# iF11K.net
KiCad netlist of a schematic drawn in Altium Designer
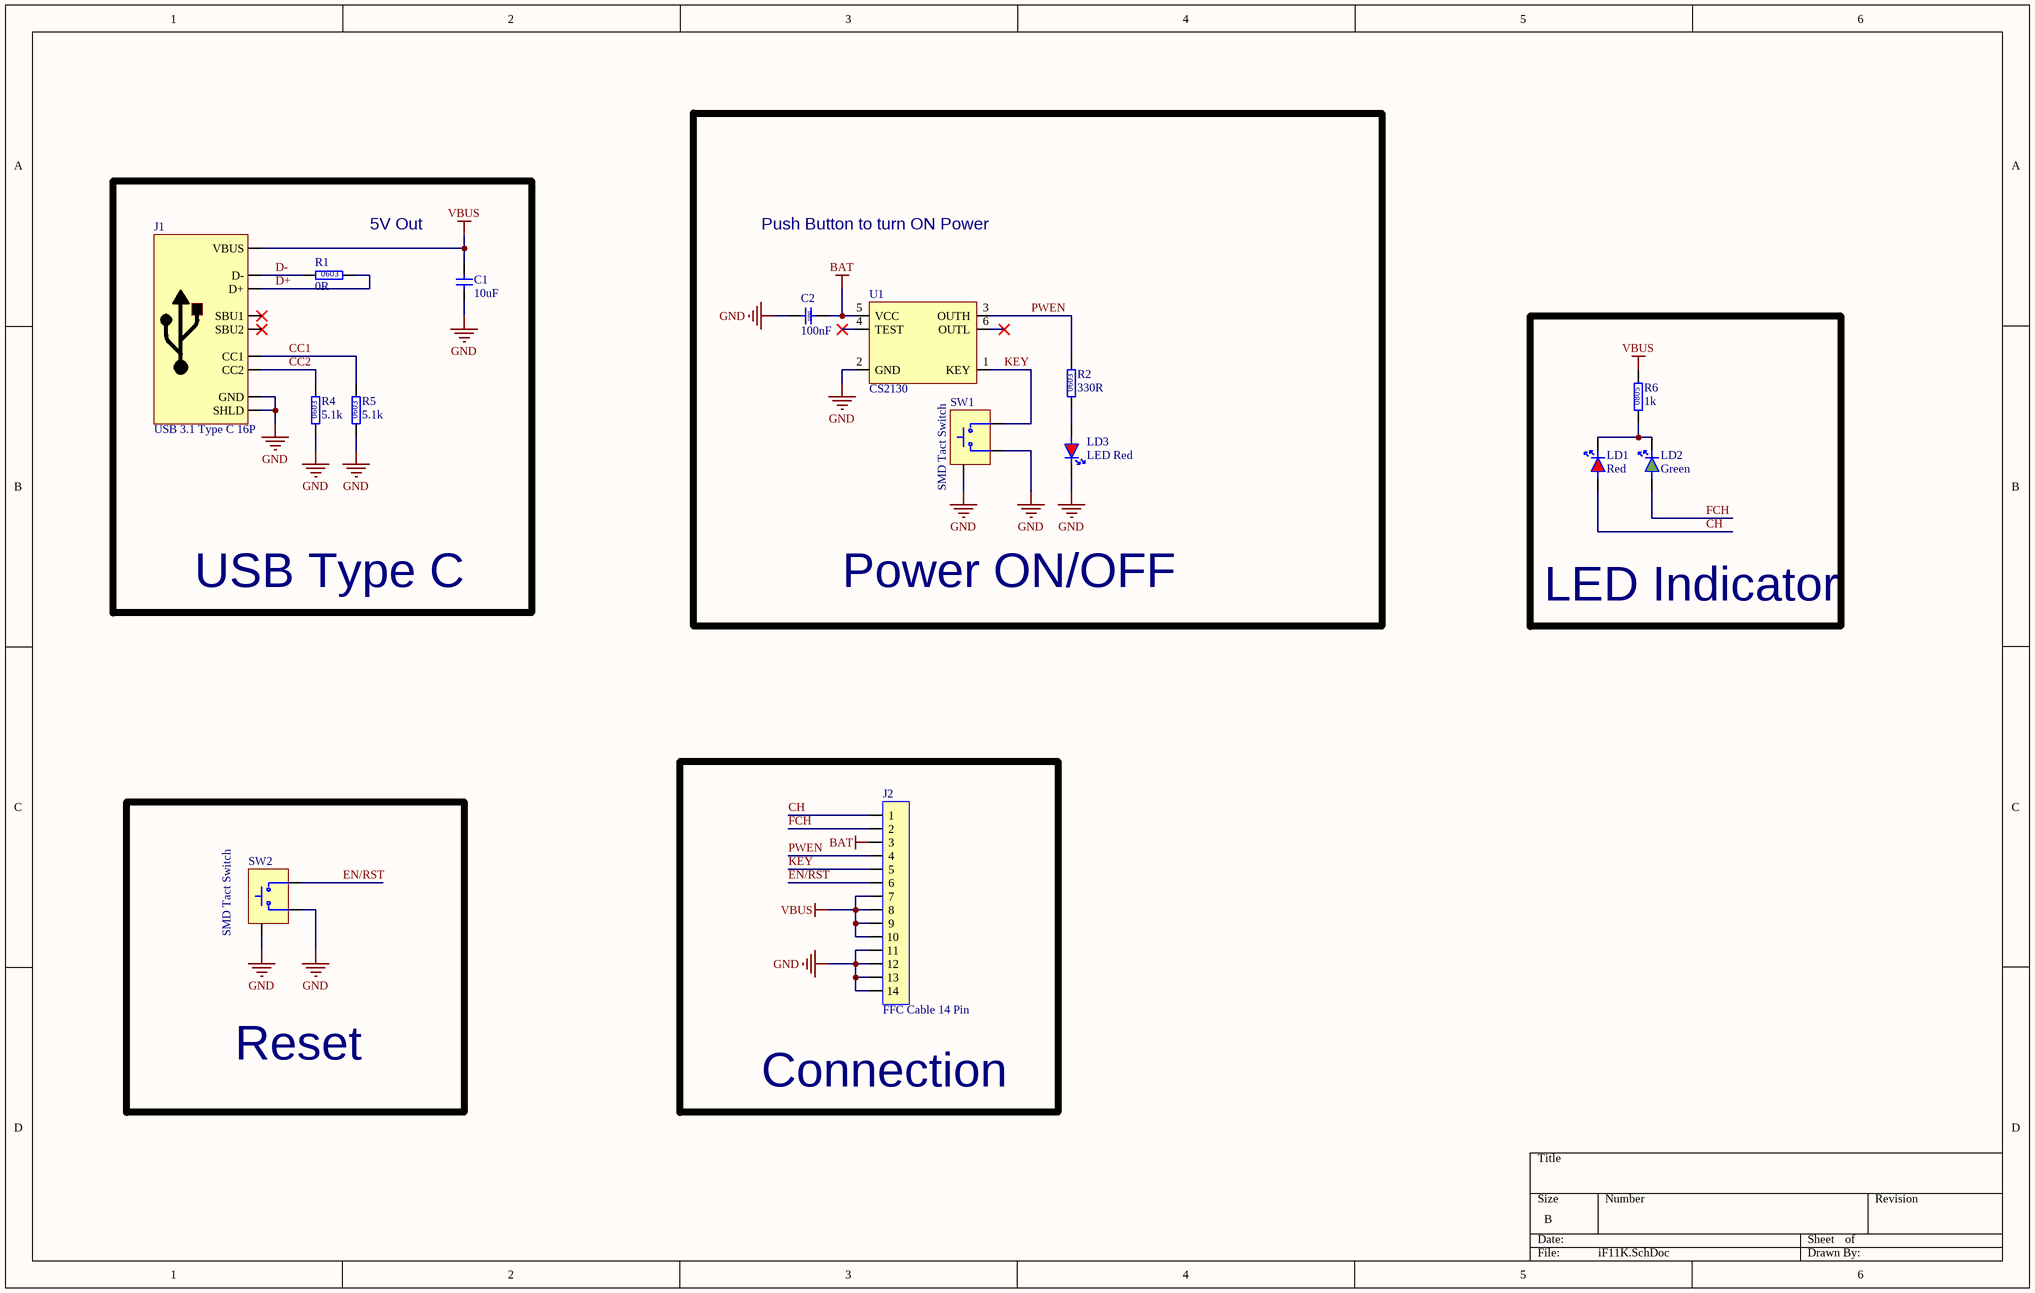
[diagram p0: iF11K.SchDoc]

(export (version "E")
  (design (tool "Eeschema 10.0.6"))
  (components
    (comp (ref "C1")
      (value "10uF")
      (footprint "C0603")
      (description "0603 Package 25V")
      (libsource (lib "Capacitors") (part "Capacitor"))
    )
    (comp (ref "C2")
      (value "100nF")
      (footprint "C0603")
      (description "10% 50V")
      (fields (field (name "PART NO") "W-T-CA-X703N100K50VNT") (field (name "MANUFACTURER") "FENGHUA"))
      (libsource (lib "Rescap") (part "C 0603 100nF 50V"))
    )
    (comp (ref "J1")
      (value "USB 3.1 Type C 16P")
      (footprint "USBC-16P -Upd")
      (description "TYPE-C 16PIN L8.35")
      (fields (field (name "PART NO") "W-T-CN-TYPE-C 16P"))
      (libsource (lib "Connector") (part "USB-C-16P"))
    )
    (comp (ref "J2")
      (value "FFC Cable 14 Pin")
      (footprint "FFC-14-1.25mm")
      (libsource (lib "Connector") (part "FFC14P"))
    )
    (comp (ref "LD1")
      (value "Red")
      (footprint "LED 3mm RED")
      (libsource (lib "Optoelectronics") (part "LED Red"))
    )
    (comp (ref "LD2")
      (value "Green")
      (footprint "LED-0603-GREEN")
      (libsource (lib "Optoelectronics") (part "LED Green"))
    )
    (comp (ref "LD3")
      (value "LED Red")
      (footprint "LED 3mm RED")
      (libsource (lib "Optoelectronics") (part "LED Red"))
    )
    (comp (ref "R1")
      (value "0R")
      (footprint "R0603-LD")
      (description "5%")
      (fields (field (name "PART NO") "W-T-RE-RS03K0RJT") (field (name "MANUFACTURER") "贴片"))
      (libsource (lib "Rescap") (part "R 0603 0R"))
    )
    (comp (ref "R2")
      (value "330R")
      (footprint "R0603-LD")
      (description "5%")
      (fields (field (name "PART NO") "W-T-RE-RS03K331JT"))
      (libsource (lib "Rescap") (part "R 0603 330R"))
    )
    (comp (ref "R4")
      (value "5.1k")
      (footprint "R0603-LD")
      (description "5%")
      (fields (field (name "PART NO") "W-T-RE-RS03K512JT"))
      (libsource (lib "Rescap") (part "R 0603 5.1k"))
    )
    (comp (ref "R5")
      (value "5.1k")
      (footprint "R0603-LD")
      (description "5%")
      (fields (field (name "PART NO") "W-T-RE-RS03K512JT"))
      (libsource (lib "Rescap") (part "R 0603 5.1k"))
    )
    (comp (ref "R6")
      (value "1k")
      (footprint "R0805-LD")
      (description "5%")
      (fields (field (name "PART NO") "W-T-RE-RS05K121JT"))
      (libsource (lib "Rescap") (part "R 0805 1k"))
    )
    (comp (ref "SW1")
      (value "SMD Tact Switch")
      (footprint "Light button")
      (libsource (lib "Switch") (part "soft tact switch"))
    )
    (comp (ref "SW2")
      (value "SMD Tact Switch")
      (footprint "Light button")
      (libsource (lib "Switch") (part "soft tact switch"))
    )
    (comp (ref "U1")
      (value "CS2130")
      (footprint "SOT23-6")
      (description "Single-button switch IC")
      (libsource (lib "mylib2") (part "CS2130"))
    )
  )
  (nets
    (net (code "1") (name "/CC1") (class "Default")
      (node (ref "J1") (pin "4") (pinfunction "CC1_4") (pintype "passive"))
      (node (ref "R5") (pin "2") (pinfunction "2_2") (pintype "passive"))
    )
    (net (code "2") (name "/CC2") (class "Default")
      (node (ref "J1") (pin "8") (pinfunction "CC2_8") (pintype "passive"))
      (node (ref "R4") (pin "2") (pinfunction "2_2") (pintype "passive"))
    )
    (net (code "3") (name "/CH") (class "Default")
      (node (ref "J2") (pin "1") (pinfunction "1_1") (pintype "passive"))
      (node (ref "LD1") (pin "1") (pinfunction "A_1") (pintype "passive"))
    )
    (net (code "4") (name "/D+") (class "Default")
      (node (ref "J1") (pin "6") (pinfunction "D+_6") (pintype "passive"))
      (node (ref "R1") (pin "2") (pinfunction "2_2") (pintype "passive"))
    )
    (net (code "5") (name "/D-") (class "Default")
      (node (ref "J1") (pin "5") (pinfunction "D-_5") (pintype "passive"))
      (node (ref "R1") (pin "1") (pinfunction "1_1") (pintype "passive"))
    )
    (net (code "6") (name "/EN{slash}RST") (class "Default")
      (node (ref "J2") (pin "6") (pinfunction "6_6") (pintype "passive"))
      (node (ref "SW2") (pin "2") (pinfunction "2_2") (pintype "passive"))
    )
    (net (code "7") (name "/FCH") (class "Default")
      (node (ref "J2") (pin "2") (pinfunction "2_2") (pintype "passive"))
      (node (ref "LD2") (pin "1") (pinfunction "A_1") (pintype "passive"))
    )
    (net (code "8") (name "/KEY") (class "Default")
      (node (ref "J2") (pin "5") (pinfunction "5_5") (pintype "passive"))
      (node (ref "SW1") (pin "2") (pinfunction "2_2") (pintype "passive"))
      (node (ref "U1") (pin "1") (pinfunction "KEY_1") (pintype "passive"))
    )
    (net (code "9") (name "/PWEN") (class "Default")
      (node (ref "J2") (pin "4") (pinfunction "4_4") (pintype "passive"))
      (node (ref "R2") (pin "2") (pinfunction "2_2") (pintype "passive"))
      (node (ref "U1") (pin "3") (pinfunction "OUTH_3") (pintype "passive"))
    )
    (net (code "10") (name "BAT") (class "Default")
      (node (ref "C2") (pin "1") (pinfunction "1_1") (pintype "passive"))
      (node (ref "J2") (pin "3") (pinfunction "3_3") (pintype "passive"))
      (node (ref "U1") (pin "5") (pinfunction "VCC_5") (pintype "passive"))
    )
    (net (code "11") (name "GND") (class "Default")
      (node (ref "C1") (pin "1") (pinfunction "1_1") (pintype "passive"))
      (node (ref "C2") (pin "2") (pinfunction "2_2") (pintype "passive"))
      (node (ref "J1") (pin "1") (pinfunction "GND_1") (pintype "passive"))
      (node (ref "J1") (pin "10") (pinfunction "SHLD_10") (pintype "passive"))
      (node (ref "J2") (pin "11") (pinfunction "11_11") (pintype "passive"))
      (node (ref "J2") (pin "12") (pinfunction "12_12") (pintype "passive"))
      (node (ref "J2") (pin "13") (pinfunction "13_13") (pintype "passive"))
      (node (ref "J2") (pin "14") (pinfunction "14_14") (pintype "passive"))
      (node (ref "LD3") (pin "2") (pinfunction "K_2") (pintype "passive"))
      (node (ref "R4") (pin "1") (pinfunction "1_1") (pintype "passive"))
      (node (ref "R5") (pin "1") (pinfunction "1_1") (pintype "passive"))
      (node (ref "SW1") (pin "1") (pinfunction "1_1") (pintype "passive"))
      (node (ref "SW1") (pin "3") (pinfunction "3_3") (pintype "passive"))
      (node (ref "SW2") (pin "1") (pinfunction "1_1") (pintype "passive"))
      (node (ref "SW2") (pin "3") (pinfunction "3_3") (pintype "passive"))
      (node (ref "U1") (pin "2") (pinfunction "GND_2") (pintype "passive"))
    )
    (net (code "12") (name "Net-(LD1-K)") (class "Default")
      (node (ref "LD1") (pin "2") (pinfunction "K_2") (pintype "passive"))
      (node (ref "LD2") (pin "2") (pinfunction "K_2") (pintype "passive"))
      (node (ref "R6") (pin "1") (pinfunction "1_1") (pintype "passive"))
    )
    (net (code "13") (name "Net-(LD3-A)") (class "Default")
      (node (ref "LD3") (pin "1") (pinfunction "A_1") (pintype "passive"))
      (node (ref "R2") (pin "1") (pinfunction "1_1") (pintype "passive"))
    )
    (net (code "14") (name "VBUS") (class "Default")
      (node (ref "C1") (pin "2") (pinfunction "2_2") (pintype "passive"))
      (node (ref "J1") (pin "2") (pinfunction "VBUS_2") (pintype "passive"))
      (node (ref "J2") (pin "10") (pinfunction "10_10") (pintype "passive"))
      (node (ref "J2") (pin "7") (pinfunction "7_7") (pintype "passive"))
      (node (ref "J2") (pin "8") (pinfunction "8_8") (pintype "passive"))
      (node (ref "J2") (pin "9") (pinfunction "9_9") (pintype "passive"))
      (node (ref "R6") (pin "2") (pinfunction "2_2") (pintype "passive"))
    )
    (net (code "15") (name "unconnected-(J1-SBU1-Pad7)") (class "Default")
      (node (ref "J1") (pin "7") (pinfunction "SBU1_7") (pintype "passive+no_connect"))
    )
    (net (code "16") (name "unconnected-(J1-SBU2-Pad3)") (class "Default")
      (node (ref "J1") (pin "3") (pinfunction "SBU2_3") (pintype "passive+no_connect"))
    )
    (net (code "17") (name "unconnected-(U1-OUTL-Pad6)") (class "Default")
      (node (ref "U1") (pin "6") (pinfunction "OUTL_6") (pintype "passive+no_connect"))
    )
    (net (code "18") (name "unconnected-(U1-TEST-Pad4)") (class "Default")
      (node (ref "U1") (pin "4") (pinfunction "TEST_4") (pintype "passive+no_connect"))
    )
  )
)
